# boxiangf-SMD.net
KiCad netlist of a schematic drawn in EAGLE
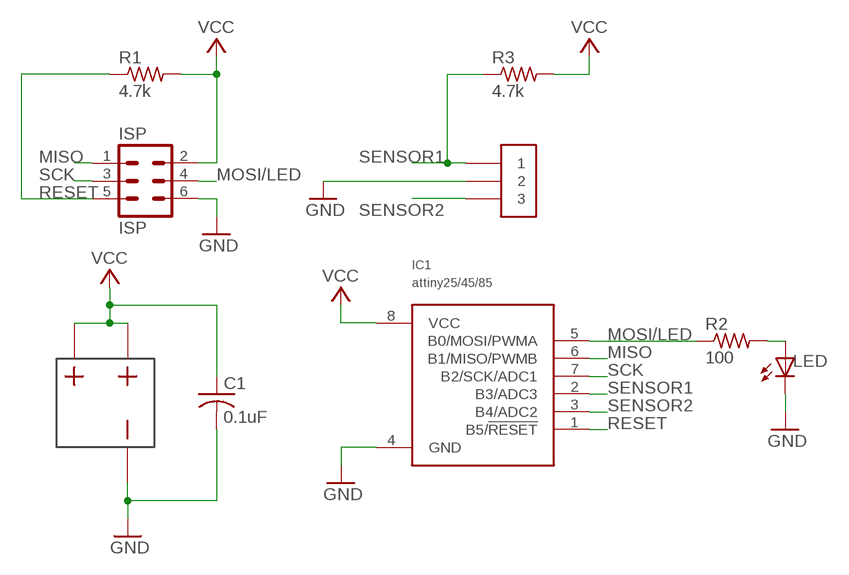
[diagram p0: schematic, sheet 1]

(export (version "E")
  (design (tool "Eeschema 10.0.6"))
  (components
    (comp (ref "C1")
      (value "0.1uF")
      (footprint "eagle-import:C0402")
      (libsource (lib "eagle-import") (part "CAPACITORSM_CAP"))
    )
    (comp (ref "IC1")
      (value "attiny25/45/85")
      (footprint "eagle-import:8S1")
      (libsource (lib "eagle-import") (part "ATTINY25SM_ATTINY"))
    )
    (comp (ref "ISP")
      (value "ISP")
      (footprint "eagle-import:SM6PIN")
      (libsource (lib "eagle-import") (part "6PINCON_ISPSM_6PIN"))
    )
    (comp (ref "LED")
      (value "LEDSMLED")
      (footprint "eagle-import:CHIPLED_0603")
      (libsource (lib "eagle-import") (part "LEDSMLED"))
    )
    (comp (ref "R1")
      (value "4.7k")
      (footprint "eagle-import:R0402")
      (libsource (lib "eagle-import") (part "RESISTORSMRESISTOR"))
    )
    (comp (ref "R2")
      (value "100")
      (footprint "eagle-import:R0402")
      (libsource (lib "eagle-import") (part "RESISTORSMRESISTOR"))
    )
    (comp (ref "R3")
      (value "4.7k")
      (footprint "eagle-import:R0402")
      (libsource (lib "eagle-import") (part "RESISTORSMRESISTOR"))
    )
    (comp (ref "SENSE")
      (value "3PINCONSM_3PIN")
      (footprint "eagle-import:SM3PIN")
      (libsource (lib "eagle-import") (part "3PINCONSM_3PIN"))
    )
    (comp (ref "US1")
      (value "BATTERYSM_BA2032")
      (footprint "eagle-import:BA2032SM")
      (libsource (lib "eagle-import") (part "BATTERYSM_BA2032"))
    )
  )
  (nets
    (net (code "1") (name "/MISO") (class "Default")
      (node (ref "IC1") (pin "6") (pinfunction "B1/MISO/PWMB_6") (pintype "bidirectional"))
      (node (ref "ISP") (pin "1") (pinfunction "1_1") (pintype "bidirectional"))
    )
    (net (code "2") (name "/MOSI{slash}LED") (class "Default")
      (node (ref "IC1") (pin "5") (pinfunction "B0/MOSI/PWMA_5") (pintype "bidirectional"))
      (node (ref "ISP") (pin "4") (pinfunction "4_4") (pintype "bidirectional"))
      (node (ref "R2") (pin "1") (pinfunction "1_1") (pintype "bidirectional"))
    )
    (net (code "3") (name "/RESET") (class "Default")
      (node (ref "IC1") (pin "1") (pinfunction "B5/~{RESET}_1") (pintype "bidirectional"))
      (node (ref "ISP") (pin "5") (pinfunction "5_5") (pintype "bidirectional"))
      (node (ref "R1") (pin "1") (pinfunction "1_1") (pintype "bidirectional"))
    )
    (net (code "4") (name "/SCK") (class "Default")
      (node (ref "IC1") (pin "7") (pinfunction "B2/SCK/ADC1_7") (pintype "bidirectional"))
      (node (ref "ISP") (pin "3") (pinfunction "3_3") (pintype "bidirectional"))
    )
    (net (code "5") (name "/SENSOR1") (class "Default")
      (node (ref "IC1") (pin "2") (pinfunction "B3/ADC3_2") (pintype "bidirectional"))
      (node (ref "R3") (pin "1") (pinfunction "1_1") (pintype "bidirectional"))
      (node (ref "SENSE") (pin "1") (pinfunction "1_1") (pintype "bidirectional"))
    )
    (net (code "6") (name "/SENSOR2") (class "Default")
      (node (ref "IC1") (pin "3") (pinfunction "B4/ADC2_3") (pintype "bidirectional"))
      (node (ref "SENSE") (pin "3") (pinfunction "3_3") (pintype "bidirectional"))
    )
    (net (code "7") (name "GND") (class "Default")
      (node (ref "C1") (pin "2") (pinfunction "2_2") (pintype "bidirectional"))
      (node (ref "IC1") (pin "4") (pinfunction "GND_4") (pintype "bidirectional"))
      (node (ref "ISP") (pin "6") (pinfunction "6_6") (pintype "bidirectional"))
      (node (ref "LED") (pin "C") (pinfunction "C_C") (pintype "bidirectional"))
      (node (ref "SENSE") (pin "2") (pinfunction "2_2") (pintype "bidirectional"))
      (node (ref "US1") (pin "1") (pinfunction "P$1_1") (pintype "bidirectional"))
    )
    (net (code "8") (name "Net-(LED-PadA)") (class "Default")
      (node (ref "LED") (pin "A") (pinfunction "A_A") (pintype "bidirectional"))
      (node (ref "R2") (pin "2") (pinfunction "2_2") (pintype "bidirectional"))
    )
    (net (code "9") (name "VCC") (class "Default")
      (node (ref "C1") (pin "1") (pinfunction "1_1") (pintype "bidirectional"))
      (node (ref "IC1") (pin "8") (pinfunction "VCC_8") (pintype "bidirectional"))
      (node (ref "ISP") (pin "2") (pinfunction "2_2") (pintype "bidirectional"))
      (node (ref "R1") (pin "2") (pinfunction "2_2") (pintype "bidirectional"))
      (node (ref "R3") (pin "2") (pinfunction "2_2") (pintype "bidirectional"))
      (node (ref "US1") (pin "2") (pinfunction "P$2_2") (pintype "bidirectional"))
      (node (ref "US1") (pin "3") (pinfunction "P$3_3") (pintype "bidirectional"))
    )
  )
)
